# 20_Conector_USB.net
KiCad netlist of a schematic drawn in Altium Designer
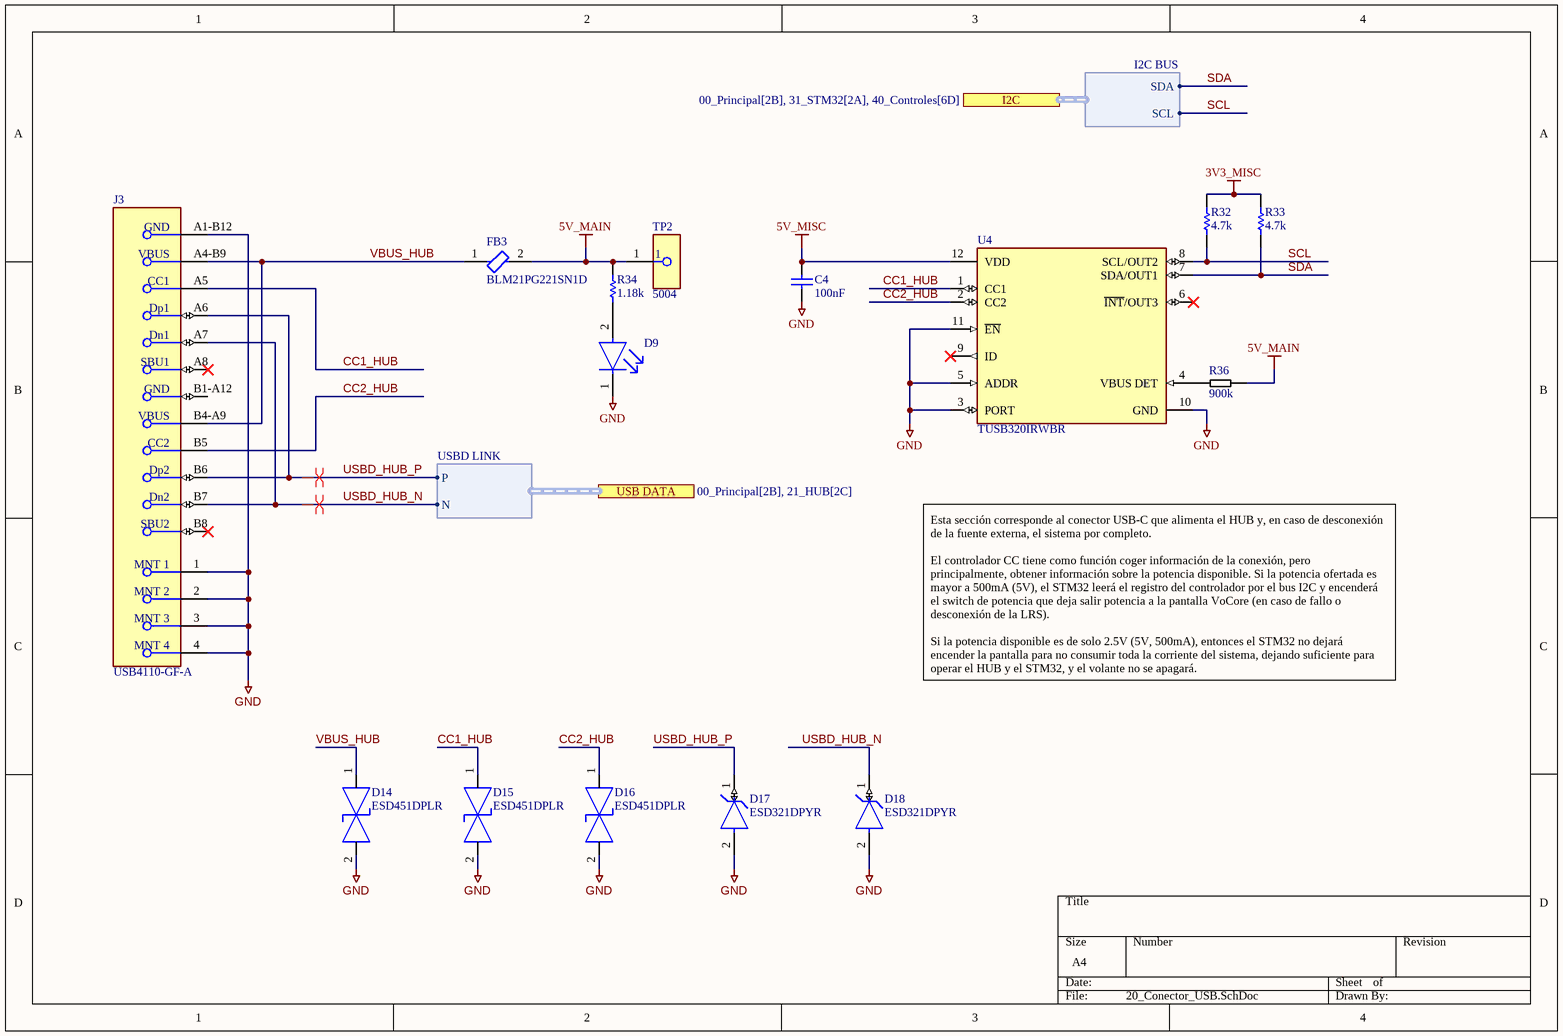
[diagram p0: 20_Conector_USB.SchDoc]

(export (version "E")
  (design (tool "Eeschema 10.0.6"))
  (components
    (comp (ref "C4")
      (value "100nF")
      (footprint "CAPC1005X55X25NL05T05")
      (fields (field (name "MANUFACTURER") "Vitramon") (field (name "PART NUMBER") "VJ0402Y104KXJCW1BC"))
      (libsource (lib "Altium Content Vault") (part "CAP"))
    )
    (comp (ref "D9")
      (value "APHD1608LZGCK")
      (footprint "FP-APHD1608LZGCK-MFG")
      (description "LED GREEN CLEAR 1608 SMD")
      (libsource (lib "Altium Content Vault") (part "8706943c75ba83719d021d2fdc84c58"))
    )
    (comp (ref "D14")
      (value "ESD451DPLR")
      (footprint "FP-DPL0002A_MFG")
      (description "0.5-pF, 5.5-V, 30-KV bidirectional ESD protection device in 0201 package 2-X2SON -40 to 125")
      (libsource (lib "Altium Content Vault") (part "ef80418522d6051962dd4b26d32e366"))
    )
    (comp (ref "D15")
      (value "ESD451DPLR")
      (footprint "FP-DPL0002A_MFG")
      (description "0.5-pF, 5.5-V, 30-KV bidirectional ESD protection device in 0201 package 2-X2SON -40 to 125")
      (libsource (lib "Altium Content Vault") (part "ef80418522d6051962dd4b26d32e366"))
    )
    (comp (ref "D16")
      (value "ESD451DPLR")
      (footprint "FP-DPL0002A_MFG")
      (description "0.5-pF, 5.5-V, 30-KV bidirectional ESD protection device in 0201 package 2-X2SON -40 to 125")
      (libsource (lib "Altium Content Vault") (part "ef80418522d6051962dd4b26d32e366"))
    )
    (comp (ref "D17")
      (value "ESD321DPYR")
      (footprint "FP-DPY0002A-MFG")
      (description "HDMI2.0 ESD PROTECTION")
      (fields
        (field (name "OCTOPART") "https://octopart.com/esd321dpyr-texas+instruments-94354200")
        (field (name "MANUFACTURER") "Texas Instruments")
      )
      (libsource (lib "Altium Content Vault") (part "66ee42db3b8e3650e8893baa18e0b41"))
    )
    (comp (ref "D18")
      (value "ESD321DPYR")
      (footprint "FP-DPY0002A-MFG")
      (description "HDMI2.0 ESD PROTECTION")
      (fields
        (field (name "OCTOPART") "https://octopart.com/esd321dpyr-texas+instruments-94354200")
        (field (name "MANUFACTURER") "Texas Instruments")
      )
      (libsource (lib "Altium Content Vault") (part "66ee42db3b8e3650e8893baa18e0b41"))
    )
    (comp (ref "FB3")
      (value "BLM21PG221SN1D")
      (footprint "FP-BLM21-0_2-t0_85-e0_5-IPC_B")
      (description "Chip Ferrite Bead, 0805, 220Ω @ 100MHz, 0.045Ω, 25%, 2A")
      (fields (field (name "TOLERANCE") "25%"))
      (libsource (lib "Altium Content Vault") (part "5f30dd21d616792df468990f7003faa"))
    )
    (comp (ref "J3")
      (value "USB4110-GF-A")
      (footprint "FP-USB4110-GF-A-MFG")
      (description "CONN USB 2.0 TYPE-C R/A SMT")
      (fields
        (field (name "OCTOPART") "https://octopart.com/usb4110-gf-a-gct-103941985")
        (field (name "MANUFACTURER") "GCT")
      )
      (libsource (lib "Altium Content Vault") (part "e23f2b38bb3c3f98e683ebab9ede730"))
    )
    (comp (ref "R32")
      (value "4.7k")
      (footprint "RESC1005X40X25ML05T10")
      (fields (field (name "MANUFACTURER") "Panasonic") (field (name "PART NUMBER") "ERJ-S02F4701X"))
      (libsource (lib "Altium Content Vault") (part "RES"))
    )
    (comp (ref "R33")
      (value "4.7k")
      (footprint "RESC1005X40X25ML05T10")
      (fields (field (name "MANUFACTURER") "Panasonic") (field (name "PART NUMBER") "ERJ-S02F4701X"))
      (libsource (lib "Altium Content Vault") (part "RES"))
    )
    (comp (ref "R34")
      (value "1.18k")
      (footprint "RESC1005X40X25NL05T05")
      (fields (field (name "PART NUMBER") "ERJ-2RKF1181X") (field (name "MANUFACTURER") "Panasonic"))
      (libsource (lib "Altium Content Vault") (part "RES"))
    )
    (comp (ref "R36")
      (value "900k")
      (footprint "RES 1206")
      (description "900k Resistor 200V 1206 0.5%")
      (libsource (lib "Esquemas") (part "RT1206CRE07900KL"))
    )
    (comp (ref "TP2")
      (value "5004")
      (footprint "FP-5004-MFG")
      (description "PC TEST POINT MINIATURE YELLOW")
      (fields
        (field (name "MANUFACTURER") "Keystone")
        (field (name "OCTOPART") "https://octopart.com/5004-keystone-28591")
      )
      (libsource (lib "Altium Content Vault") (part "98815daf2f2c152b0c43f5ab9800df6"))
    )
    (comp (ref "U4")
      (value "TUSB320IRWBR")
      (footprint "FP-RWB0012A-MFG")
      (description "IC INTERFACE SPECIALIZED 12X2QFN")
      (libsource (lib "Altium Content Vault") (part "76af6d7f95a64df20dc6dc148ef600c"))
    )
  )
  (nets
    (net (code "5") (name "/CC1_HUB") (class "Default")
      (node (ref "D15") (pin "1") (pinfunction "1_IO_1") (pintype "passive"))
      (node (ref "J3") (pin "A5") (pinfunction "CC1_A5") (pintype "passive"))
      (node (ref "U4") (pin "1") (pinfunction "CC1_1") (pintype "bidirectional"))
    )
    (net (code "6") (name "/CC2_HUB") (class "Default")
      (node (ref "D16") (pin "1") (pinfunction "1_IO_1") (pintype "passive"))
      (node (ref "J3") (pin "B5") (pinfunction "CC2_B5") (pintype "passive"))
      (node (ref "U4") (pin "2") (pinfunction "CC2_2") (pintype "bidirectional"))
    )
    (net (code "7") (name "/SCL") (class "Default")
      (node (ref "R32") (pin "1") (pinfunction "1_1") (pintype "passive"))
      (node (ref "U4") (pin "8") (pinfunction "SCL/OUT2_8") (pintype "bidirectional"))
    )
    (net (code "8") (name "/SDA") (class "Default")
      (node (ref "R33") (pin "1") (pinfunction "1_1") (pintype "passive"))
      (node (ref "U4") (pin "7") (pinfunction "SDA/OUT1_7") (pintype "bidirectional"))
    )
    (net (code "9") (name "/USBD_HUB_N") (class "Default")
      (node (ref "D18") (pin "1") (pinfunction "IO_1") (pintype "bidirectional"))
      (node (ref "J3") (pin "A7") (pinfunction "Dn1_A7") (pintype "bidirectional"))
      (node (ref "J3") (pin "B7") (pinfunction "Dn2_B7") (pintype "bidirectional"))
    )
    (net (code "10") (name "/USBD_HUB_P") (class "Default")
      (node (ref "D17") (pin "1") (pinfunction "IO_1") (pintype "bidirectional"))
      (node (ref "J3") (pin "A6") (pinfunction "Dp1_A6") (pintype "bidirectional"))
      (node (ref "J3") (pin "B6") (pinfunction "Dp2_B6") (pintype "bidirectional"))
    )
    (net (code "11") (name "/VBUS_HUB") (class "Default")
      (node (ref "D14") (pin "1") (pinfunction "1_IO_1") (pintype "passive"))
      (node (ref "FB3") (pin "1") (pinfunction "1_1") (pintype "passive"))
      (node (ref "J3") (pin "A4-B9") (pinfunction "VBUS_A4-B9") (pintype "power_in"))
      (node (ref "J3") (pin "B4-A9") (pinfunction "VBUS_B4-A9") (pintype "power_in"))
    )
    (net (code "14") (name "3V3_MISC") (class "Default")
      (node (ref "R32") (pin "2") (pinfunction "2_2") (pintype "passive"))
      (node (ref "R33") (pin "2") (pinfunction "2_2") (pintype "passive"))
    )
    (net (code "15") (name "5V_MAIN") (class "Default")
      (node (ref "FB3") (pin "2") (pinfunction "2_2") (pintype "passive"))
      (node (ref "R34") (pin "2") (pinfunction "2_2") (pintype "passive"))
      (node (ref "R36") (pin "1") (pintype "passive"))
      (node (ref "TP2") (pin "1") (pinfunction "1_1") (pintype "passive"))
    )
    (net (code "16") (name "5V_MISC") (class "Default")
      (node (ref "C4") (pin "2") (pinfunction "2_2") (pintype "passive"))
      (node (ref "U4") (pin "12") (pinfunction "VDD_12") (pintype "power_in"))
    )
    (net (code "17") (name "GND") (class "Default")
      (node (ref "C4") (pin "1") (pinfunction "1_1") (pintype "passive"))
      (node (ref "D14") (pin "2") (pinfunction "2_IO_2") (pintype "passive"))
      (node (ref "D15") (pin "2") (pinfunction "2_IO_2") (pintype "passive"))
      (node (ref "D16") (pin "2") (pinfunction "2_IO_2") (pintype "passive"))
      (node (ref "D17") (pin "2") (pinfunction "GND_2") (pintype "power_in"))
      (node (ref "D18") (pin "2") (pinfunction "GND_2") (pintype "power_in"))
      (node (ref "D9") (pin "1") (pinfunction "C_1") (pintype "passive"))
      (node (ref "J3") (pin "1") (pinfunction "MNT_1_1") (pintype "passive"))
      (node (ref "J3") (pin "2") (pinfunction "MNT_2_2") (pintype "passive"))
      (node (ref "J3") (pin "3") (pinfunction "MNT_3_3") (pintype "passive"))
      (node (ref "J3") (pin "4") (pinfunction "MNT_4_4") (pintype "passive"))
      (node (ref "J3") (pin "A1-B12") (pinfunction "GND_A1-B12") (pintype "passive"))
      (node (ref "U4") (pin "10") (pinfunction "GND_10") (pintype "power_in"))
      (node (ref "U4") (pin "11") (pinfunction "~{EN}_11") (pintype "input"))
      (node (ref "U4") (pin "3") (pinfunction "PORT_3") (pintype "bidirectional"))
      (node (ref "U4") (pin "5") (pinfunction "ADDR_5") (pintype "input"))
    )
    (net (code "18") (name "Net-(D9-A)") (class "Default")
      (node (ref "D9") (pin "2") (pinfunction "A_2") (pintype "passive"))
      (node (ref "R34") (pin "1") (pinfunction "1_1") (pintype "passive"))
    )
    (net (code "19") (name "Net-(U4-VBUS_DET)") (class "Default")
      (node (ref "R36") (pin "2") (pintype "passive"))
      (node (ref "U4") (pin "4") (pinfunction "VBUS_DET_4") (pintype "input"))
    )
    (net (code "20") (name "unconnected-(J3-GND-PadB1-A12)") (class "Default")
      (node (ref "J3") (pin "B1-A12") (pinfunction "GND_B1-A12") (pintype "bidirectional"))
    )
    (net (code "21") (name "unconnected-(J3-SBU1-PadA8)") (class "Default")
      (node (ref "J3") (pin "A8") (pinfunction "SBU1_A8") (pintype "bidirectional+no_connect"))
    )
    (net (code "22") (name "unconnected-(J3-SBU2-PadB8)") (class "Default")
      (node (ref "J3") (pin "B8") (pinfunction "SBU2_B8") (pintype "bidirectional+no_connect"))
    )
    (net (code "23") (name "unconnected-(U4-ID-Pad9)") (class "Default")
      (node (ref "U4") (pin "9") (pinfunction "ID_9") (pintype "output+no_connect"))
    )
    (net (code "24") (name "unconnected-(U4-~{INT}{slash}OUT3-Pad6)") (class "Default")
      (node (ref "U4") (pin "6") (pinfunction "~{INT}/OUT3_6") (pintype "bidirectional+no_connect"))
    )
  )
)
